# Interfacing_board_updated.net
KiCad netlist of a schematic drawn in EAGLE
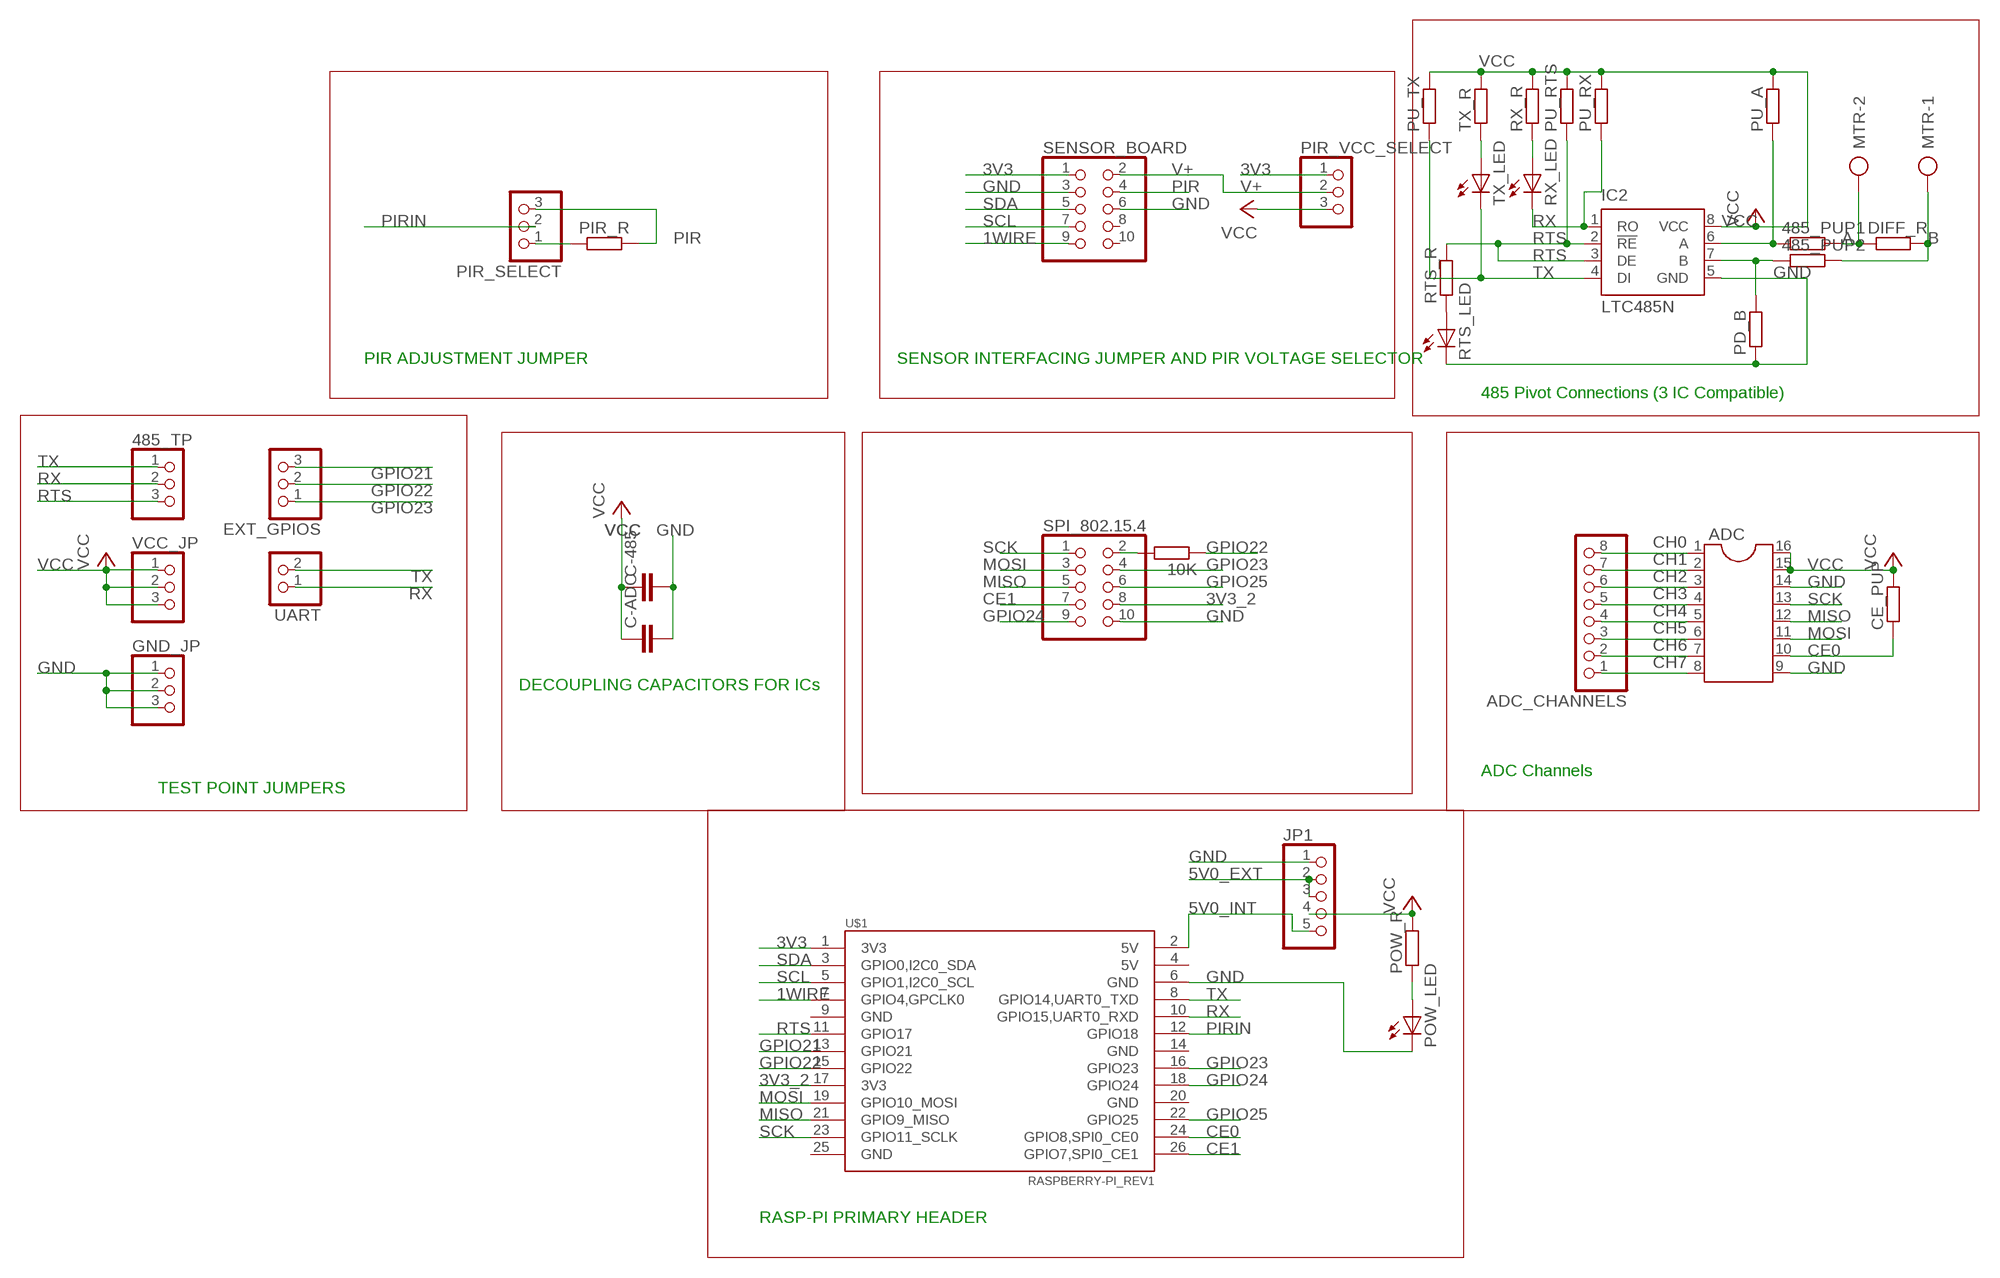
[diagram p0: schematic, sheet 1]

(export (version "E")
  (design (tool "Eeschema 10.0.6"))
  (components
    (comp (ref "10K")
      (value "R-EU_R0603")
      (footprint "eagle-import:R0603")
      (libsource (lib "eagle-import") (part "R-EU_R0603"))
    )
    (comp (ref "485_PUP1")
      (value "R-EU_R0603")
      (footprint "eagle-import:R0603")
      (libsource (lib "eagle-import") (part "R-EU_R0603"))
    )
    (comp (ref "485_PUP2")
      (value "R-EU_R0603")
      (footprint "eagle-import:R0603")
      (libsource (lib "eagle-import") (part "R-EU_R0603"))
    )
    (comp (ref "485_TP")
      (value "PINHD-1X3/90")
      (footprint "eagle-import:1X03_90")
      (libsource (lib "eagle-import") (part "PINHD-1X3/90"))
    )
    (comp (ref "ADC")
      (value "DIL16")
      (footprint "eagle-import:DIL16")
      (libsource (lib "eagle-import") (part "DIL16"))
    )
    (comp (ref "ADC_CHANNELS")
      (value "PINHD-1X8/90")
      (footprint "eagle-import:1X08_90")
      (libsource (lib "eagle-import") (part "PINHD-1X8/90"))
    )
    (comp (ref "C-485")
      (value "C-EU025-025X050")
      (footprint "eagle-import:C025-025X050")
      (libsource (lib "eagle-import") (part "C-EU025-025X050"))
    )
    (comp (ref "C-ADC")
      (value "C-EU025-025X050")
      (footprint "eagle-import:C025-025X050")
      (libsource (lib "eagle-import") (part "C-EU025-025X050"))
    )
    (comp (ref "CE_PUP")
      (value "R-EU_R0603")
      (footprint "eagle-import:R0603")
      (libsource (lib "eagle-import") (part "R-EU_R0603"))
    )
    (comp (ref "DIFF_R")
      (value "R-EU_R0603")
      (footprint "eagle-import:R0603")
      (libsource (lib "eagle-import") (part "R-EU_R0603"))
    )
    (comp (ref "EXT_GPIOS")
      (value "PINHD-1X3/90")
      (footprint "eagle-import:1X03_90")
      (libsource (lib "eagle-import") (part "PINHD-1X3/90"))
    )
    (comp (ref "GND_JP")
      (value "PINHD-1X3/90")
      (footprint "eagle-import:1X03_90")
      (libsource (lib "eagle-import") (part "PINHD-1X3/90"))
    )
    (comp (ref "IC2")
      (value "LTC485N")
      (footprint "eagle-import:DIL08")
      (libsource (lib "eagle-import") (part "LTC485N"))
    )
    (comp (ref "JP1")
      (value "PINHD-1X5")
      (footprint "eagle-import:1X05")
      (libsource (lib "eagle-import") (part "PINHD-1X5"))
    )
    (comp (ref "MTR")
      (value "AK500/2-H")
      (footprint "eagle-import:AK500_2-H")
      (libsource (lib "eagle-import") (part "AK500/2-H"))
    )
    (comp (ref "PD_B")
      (value "R-EU_R0603")
      (footprint "eagle-import:R0603")
      (libsource (lib "eagle-import") (part "R-EU_R0603"))
    )
    (comp (ref "PIR_R")
      (value "R-EU_R0603")
      (footprint "eagle-import:R0603")
      (libsource (lib "eagle-import") (part "R-EU_R0603"))
    )
    (comp (ref "PIR_SELECT")
      (value "PINHD-1X3/90")
      (footprint "eagle-import:1X03_90")
      (libsource (lib "eagle-import") (part "PINHD-1X3/90"))
    )
    (comp (ref "PIR_VCC_SELECT")
      (value "PINHD-1X3/90")
      (footprint "eagle-import:1X03_90")
      (libsource (lib "eagle-import") (part "PINHD-1X3/90"))
    )
    (comp (ref "POW_LED")
      (value "LEDCHIPLED_0805")
      (footprint "eagle-import:CHIPLED_0805")
      (libsource (lib "eagle-import") (part "LEDCHIPLED_0805"))
    )
    (comp (ref "POW_R")
      (value "R-EU_R0603")
      (footprint "eagle-import:R0603")
      (libsource (lib "eagle-import") (part "R-EU_R0603"))
    )
    (comp (ref "PU_A")
      (value "R-EU_R0603")
      (footprint "eagle-import:R0603")
      (libsource (lib "eagle-import") (part "R-EU_R0603"))
    )
    (comp (ref "PU_RTS")
      (value "R-EU_R0603")
      (footprint "eagle-import:R0603")
      (libsource (lib "eagle-import") (part "R-EU_R0603"))
    )
    (comp (ref "PU_RX")
      (value "R-EU_R0603")
      (footprint "eagle-import:R0603")
      (libsource (lib "eagle-import") (part "R-EU_R0603"))
    )
    (comp (ref "PU_TX")
      (value "R-EU_R0603")
      (footprint "eagle-import:R0603")
      (libsource (lib "eagle-import") (part "R-EU_R0603"))
    )
    (comp (ref "RTS_LED")
      (value "LEDCHIPLED_0805")
      (footprint "eagle-import:CHIPLED_0805")
      (libsource (lib "eagle-import") (part "LEDCHIPLED_0805"))
    )
    (comp (ref "RTS_R")
      (value "R-EU_R0603")
      (footprint "eagle-import:R0603")
      (libsource (lib "eagle-import") (part "R-EU_R0603"))
    )
    (comp (ref "RX_LED")
      (value "LEDCHIPLED_0805")
      (footprint "eagle-import:CHIPLED_0805")
      (libsource (lib "eagle-import") (part "LEDCHIPLED_0805"))
    )
    (comp (ref "RX_R")
      (value "R-EU_R0603")
      (footprint "eagle-import:R0603")
      (libsource (lib "eagle-import") (part "R-EU_R0603"))
    )
    (comp (ref "SENSOR_BOARD")
      (value "PINHD-2X5/90")
      (footprint "eagle-import:2X05_90")
      (libsource (lib "eagle-import") (part "PINHD-2X5/90"))
    )
    (comp (ref "SPI_802.15.4")
      (value "PINHD-2X5/90")
      (footprint "eagle-import:2X05_90")
      (libsource (lib "eagle-import") (part "PINHD-2X5/90"))
    )
    (comp (ref "TX_LED")
      (value "LEDCHIPLED_0805")
      (footprint "eagle-import:CHIPLED_0805")
      (libsource (lib "eagle-import") (part "LEDCHIPLED_0805"))
    )
    (comp (ref "TX_R")
      (value "R-EU_R0603")
      (footprint "eagle-import:R0603")
      (libsource (lib "eagle-import") (part "R-EU_R0603"))
    )
    (comp (ref "U$1")
      (value "RASPBERRY-PI_REV1")
      (footprint "eagle-import:RASPBERRY-PI_REV1")
      (libsource (lib "eagle-import") (part "RASPBERRY-PI_REV1"))
    )
    (comp (ref "UART")
      (value "PINHD-1X2")
      (footprint "eagle-import:1X02")
      (libsource (lib "eagle-import") (part "PINHD-1X2"))
    )
    (comp (ref "VCC_JP")
      (value "PINHD-1X3/90")
      (footprint "eagle-import:1X03_90")
      (libsource (lib "eagle-import") (part "PINHD-1X3/90"))
    )
  )
  (nets
    (net (code "1") (name "/1WIRE") (class "Default")
      (node (ref "SENSOR_BOARD") (pin "9") (pinfunction "9_9") (pintype "passive"))
      (node (ref "U$1") (pin "7") (pinfunction "GPIO4,GPCLK0_7") (pintype "bidirectional"))
    )
    (net (code "2") (name "/3V3") (class "Default")
      (node (ref "PIR_VCC_SELECT") (pin "1") (pinfunction "1_1") (pintype "passive"))
      (node (ref "SENSOR_BOARD") (pin "1") (pinfunction "1_1") (pintype "passive"))
      (node (ref "U$1") (pin "1") (pinfunction "3V3_1") (pintype "bidirectional"))
    )
    (net (code "3") (name "/3V3_2") (class "Default")
      (node (ref "SPI_802.15.4") (pin "8") (pinfunction "8_8") (pintype "passive"))
      (node (ref "U$1") (pin "17") (pinfunction "3V3_17") (pintype "bidirectional"))
    )
    (net (code "4") (name "/5V0_EXT") (class "Default")
      (node (ref "JP1") (pin "2") (pinfunction "2_2") (pintype "passive"))
      (node (ref "JP1") (pin "3") (pinfunction "3_3") (pintype "passive"))
    )
    (net (code "5") (name "/5V0_INT") (class "Default")
      (node (ref "JP1") (pin "5") (pinfunction "5_5") (pintype "passive"))
      (node (ref "U$1") (pin "2") (pinfunction "5V_2") (pintype "bidirectional"))
    )
    (net (code "6") (name "/A") (class "Default")
      (node (ref "485_PUP1") (pin "2") (pinfunction "2_2") (pintype "passive"))
      (node (ref "DIFF_R") (pin "1") (pinfunction "1_1") (pintype "passive"))
      (node (ref "MTR") (pin "2") (pinfunction "KL_2") (pintype "passive"))
    )
    (net (code "7") (name "/B") (class "Default")
      (node (ref "485_PUP2") (pin "2") (pinfunction "2_2") (pintype "passive"))
      (node (ref "DIFF_R") (pin "2") (pinfunction "2_2") (pintype "passive"))
      (node (ref "MTR") (pin "1") (pinfunction "KL_1") (pintype "passive"))
    )
    (net (code "8") (name "/CE0") (class "Default")
      (node (ref "ADC") (pin "10") (pinfunction "10_10") (pintype "passive"))
      (node (ref "CE_PUP") (pin "1") (pinfunction "1_1") (pintype "passive"))
      (node (ref "U$1") (pin "24") (pinfunction "GPIO8,SPI0_CE0_24") (pintype "bidirectional"))
    )
    (net (code "9") (name "/CE1") (class "Default")
      (node (ref "SPI_802.15.4") (pin "7") (pinfunction "7_7") (pintype "passive"))
      (node (ref "U$1") (pin "26") (pinfunction "GPIO7,SPI0_CE1_26") (pintype "bidirectional"))
    )
    (net (code "10") (name "/CH0") (class "Default")
      (node (ref "ADC") (pin "1") (pinfunction "1_1") (pintype "passive"))
      (node (ref "ADC_CHANNELS") (pin "8") (pinfunction "8_8") (pintype "passive"))
    )
    (net (code "11") (name "/CH1") (class "Default")
      (node (ref "ADC") (pin "2") (pinfunction "2_2") (pintype "passive"))
      (node (ref "ADC_CHANNELS") (pin "7") (pinfunction "7_7") (pintype "passive"))
    )
    (net (code "12") (name "/CH2") (class "Default")
      (node (ref "ADC") (pin "3") (pinfunction "3_3") (pintype "passive"))
      (node (ref "ADC_CHANNELS") (pin "6") (pinfunction "6_6") (pintype "passive"))
    )
    (net (code "13") (name "/CH3") (class "Default")
      (node (ref "ADC") (pin "4") (pinfunction "4_4") (pintype "passive"))
      (node (ref "ADC_CHANNELS") (pin "5") (pinfunction "5_5") (pintype "passive"))
    )
    (net (code "14") (name "/CH4") (class "Default")
      (node (ref "ADC") (pin "5") (pinfunction "5_5") (pintype "passive"))
      (node (ref "ADC_CHANNELS") (pin "4") (pinfunction "4_4") (pintype "passive"))
    )
    (net (code "15") (name "/CH5") (class "Default")
      (node (ref "ADC") (pin "6") (pinfunction "6_6") (pintype "passive"))
      (node (ref "ADC_CHANNELS") (pin "3") (pinfunction "3_3") (pintype "passive"))
    )
    (net (code "16") (name "/CH6") (class "Default")
      (node (ref "ADC") (pin "7") (pinfunction "7_7") (pintype "passive"))
      (node (ref "ADC_CHANNELS") (pin "2") (pinfunction "2_2") (pintype "passive"))
    )
    (net (code "17") (name "/CH7") (class "Default")
      (node (ref "ADC") (pin "8") (pinfunction "8_8") (pintype "passive"))
      (node (ref "ADC_CHANNELS") (pin "1") (pinfunction "1_1") (pintype "passive"))
    )
    (net (code "18") (name "/GND") (class "Default")
      (node (ref "ADC") (pin "14") (pinfunction "14_14") (pintype "passive"))
      (node (ref "ADC") (pin "9") (pinfunction "9_9") (pintype "passive"))
      (node (ref "C-485") (pin "2") (pinfunction "2_2") (pintype "passive"))
      (node (ref "C-ADC") (pin "2") (pinfunction "2_2") (pintype "passive"))
      (node (ref "GND_JP") (pin "1") (pinfunction "1_1") (pintype "passive"))
      (node (ref "GND_JP") (pin "2") (pinfunction "2_2") (pintype "passive"))
      (node (ref "GND_JP") (pin "3") (pinfunction "3_3") (pintype "passive"))
      (node (ref "IC2") (pin "5") (pinfunction "GND_5") (pintype "input"))
      (node (ref "JP1") (pin "1") (pinfunction "1_1") (pintype "passive"))
      (node (ref "PD_B") (pin "1") (pinfunction "1_1") (pintype "passive"))
      (node (ref "POW_LED") (pin "C") (pinfunction "C_C") (pintype "passive"))
      (node (ref "RTS_LED") (pin "C") (pinfunction "C_C") (pintype "passive"))
      (node (ref "SENSOR_BOARD") (pin "3") (pinfunction "3_3") (pintype "passive"))
      (node (ref "SENSOR_BOARD") (pin "6") (pinfunction "6_6") (pintype "passive"))
      (node (ref "SPI_802.15.4") (pin "10") (pinfunction "10_10") (pintype "passive"))
      (node (ref "U$1") (pin "6") (pinfunction "GND_6") (pintype "bidirectional"))
    )
    (net (code "19") (name "/GPIO21") (class "Default")
      (node (ref "EXT_GPIOS") (pin "3") (pinfunction "3_3") (pintype "passive"))
      (node (ref "U$1") (pin "13") (pinfunction "GPIO21_13") (pintype "bidirectional"))
    )
    (net (code "20") (name "/GPIO22") (class "Default")
      (node (ref "10K") (pin "1") (pinfunction "1_1") (pintype "passive"))
      (node (ref "EXT_GPIOS") (pin "2") (pinfunction "2_2") (pintype "passive"))
      (node (ref "U$1") (pin "15") (pinfunction "GPIO22_15") (pintype "bidirectional"))
    )
    (net (code "21") (name "/GPIO23") (class "Default")
      (node (ref "EXT_GPIOS") (pin "1") (pinfunction "1_1") (pintype "passive"))
      (node (ref "SPI_802.15.4") (pin "4") (pinfunction "4_4") (pintype "passive"))
      (node (ref "U$1") (pin "16") (pinfunction "GPIO23_16") (pintype "bidirectional"))
    )
    (net (code "22") (name "/GPIO24") (class "Default")
      (node (ref "SPI_802.15.4") (pin "9") (pinfunction "9_9") (pintype "passive"))
      (node (ref "U$1") (pin "18") (pinfunction "GPIO24_18") (pintype "bidirectional"))
    )
    (net (code "23") (name "/GPIO25") (class "Default")
      (node (ref "SPI_802.15.4") (pin "6") (pinfunction "6_6") (pintype "passive"))
      (node (ref "U$1") (pin "22") (pinfunction "GPIO25_22") (pintype "bidirectional"))
    )
    (net (code "24") (name "/MISO") (class "Default")
      (node (ref "ADC") (pin "12") (pinfunction "12_12") (pintype "passive"))
      (node (ref "SPI_802.15.4") (pin "5") (pinfunction "5_5") (pintype "passive"))
      (node (ref "U$1") (pin "21") (pinfunction "GPIO9_MISO_21") (pintype "bidirectional"))
    )
    (net (code "25") (name "/MOSI") (class "Default")
      (node (ref "ADC") (pin "11") (pinfunction "11_11") (pintype "passive"))
      (node (ref "SPI_802.15.4") (pin "3") (pinfunction "3_3") (pintype "passive"))
      (node (ref "U$1") (pin "19") (pinfunction "GPIO10_MOSI_19") (pintype "bidirectional"))
    )
    (net (code "26") (name "/PIR") (class "Default")
      (node (ref "PIR_R") (pin "2") (pinfunction "2_2") (pintype "passive"))
      (node (ref "PIR_SELECT") (pin "3") (pinfunction "3_3") (pintype "passive"))
      (node (ref "SENSOR_BOARD") (pin "4") (pinfunction "4_4") (pintype "passive"))
    )
    (net (code "27") (name "/PIRIN") (class "Default")
      (node (ref "PIR_SELECT") (pin "2") (pinfunction "2_2") (pintype "passive"))
      (node (ref "U$1") (pin "12") (pinfunction "GPIO18_12") (pintype "bidirectional"))
    )
    (net (code "28") (name "/RTS") (class "Default")
      (node (ref "485_TP") (pin "3") (pinfunction "3_3") (pintype "passive"))
      (node (ref "IC2") (pin "2") (pinfunction "~{RE}_2") (pintype "input"))
      (node (ref "IC2") (pin "3") (pinfunction "DE_3") (pintype "input"))
      (node (ref "PU_RTS") (pin "1") (pinfunction "1_1") (pintype "passive"))
      (node (ref "RTS_R") (pin "2") (pinfunction "2_2") (pintype "passive"))
      (node (ref "U$1") (pin "11") (pinfunction "GPIO17_11") (pintype "bidirectional"))
    )
    (net (code "29") (name "/RX") (class "Default")
      (node (ref "485_TP") (pin "2") (pinfunction "2_2") (pintype "passive"))
      (node (ref "IC2") (pin "1") (pinfunction "RO_1") (pintype "output"))
      (node (ref "PU_RX") (pin "1") (pinfunction "1_1") (pintype "passive"))
      (node (ref "RX_LED") (pin "C") (pinfunction "C_C") (pintype "passive"))
      (node (ref "U$1") (pin "10") (pinfunction "GPIO15,UART0_RXD_10") (pintype "bidirectional"))
      (node (ref "UART") (pin "1") (pinfunction "1_1") (pintype "passive"))
    )
    (net (code "30") (name "/SCK") (class "Default")
      (node (ref "ADC") (pin "13") (pinfunction "13_13") (pintype "passive"))
      (node (ref "SPI_802.15.4") (pin "1") (pinfunction "1_1") (pintype "passive"))
      (node (ref "U$1") (pin "23") (pinfunction "GPIO11_SCLK_23") (pintype "bidirectional"))
    )
    (net (code "31") (name "/SCL") (class "Default")
      (node (ref "SENSOR_BOARD") (pin "7") (pinfunction "7_7") (pintype "passive"))
      (node (ref "U$1") (pin "5") (pinfunction "GPIO1,I2C0_SCL_5") (pintype "bidirectional"))
    )
    (net (code "32") (name "/SDA") (class "Default")
      (node (ref "SENSOR_BOARD") (pin "5") (pinfunction "5_5") (pintype "passive"))
      (node (ref "U$1") (pin "3") (pinfunction "GPIO0,I2C0_SDA_3") (pintype "bidirectional"))
    )
    (net (code "33") (name "/TX") (class "Default")
      (node (ref "485_TP") (pin "1") (pinfunction "1_1") (pintype "passive"))
      (node (ref "IC2") (pin "4") (pinfunction "DI_4") (pintype "input"))
      (node (ref "PU_TX") (pin "1") (pinfunction "1_1") (pintype "passive"))
      (node (ref "TX_LED") (pin "C") (pinfunction "C_C") (pintype "passive"))
      (node (ref "U$1") (pin "8") (pinfunction "GPIO14,UART0_TXD_8") (pintype "bidirectional"))
      (node (ref "UART") (pin "2") (pinfunction "2_2") (pintype "passive"))
    )
    (net (code "34") (name "/V+") (class "Default")
      (node (ref "PIR_VCC_SELECT") (pin "2") (pinfunction "2_2") (pintype "passive"))
      (node (ref "SENSOR_BOARD") (pin "2") (pinfunction "2_2") (pintype "passive"))
    )
    (net (code "35") (name "Net-(10K-Pad2)") (class "Default")
      (node (ref "10K") (pin "2") (pinfunction "2_2") (pintype "passive"))
      (node (ref "SPI_802.15.4") (pin "2") (pinfunction "2_2") (pintype "passive"))
    )
    (net (code "36") (name "Net-(IC2-A)") (class "Default")
      (node (ref "485_PUP1") (pin "1") (pinfunction "1_1") (pintype "passive"))
      (node (ref "IC2") (pin "6") (pinfunction "A_6") (pintype "bidirectional"))
      (node (ref "PU_A") (pin "1") (pinfunction "1_1") (pintype "passive"))
    )
    (net (code "37") (name "Net-(IC2-B)") (class "Default")
      (node (ref "485_PUP2") (pin "1") (pinfunction "1_1") (pintype "passive"))
      (node (ref "IC2") (pin "7") (pinfunction "B_7") (pintype "bidirectional"))
      (node (ref "PD_B") (pin "2") (pinfunction "2_2") (pintype "passive"))
    )
    (net (code "38") (name "Net-(PIR_R-Pad1)") (class "Default")
      (node (ref "PIR_R") (pin "1") (pinfunction "1_1") (pintype "passive"))
      (node (ref "PIR_SELECT") (pin "1") (pinfunction "1_1") (pintype "passive"))
    )
    (net (code "39") (name "Net-(POW_LED-PadA)") (class "Default")
      (node (ref "POW_LED") (pin "A") (pinfunction "A_A") (pintype "passive"))
      (node (ref "POW_R") (pin "1") (pinfunction "1_1") (pintype "passive"))
    )
    (net (code "40") (name "Net-(RTS_LED-PadA)") (class "Default")
      (node (ref "RTS_LED") (pin "A") (pinfunction "A_A") (pintype "passive"))
      (node (ref "RTS_R") (pin "1") (pinfunction "1_1") (pintype "passive"))
    )
    (net (code "41") (name "Net-(RX_LED-PadA)") (class "Default")
      (node (ref "RX_LED") (pin "A") (pinfunction "A_A") (pintype "passive"))
      (node (ref "RX_R") (pin "1") (pinfunction "1_1") (pintype "passive"))
    )
    (net (code "42") (name "Net-(TX_LED-PadA)") (class "Default")
      (node (ref "TX_LED") (pin "A") (pinfunction "A_A") (pintype "passive"))
      (node (ref "TX_R") (pin "1") (pinfunction "1_1") (pintype "passive"))
    )
    (net (code "43") (name "VCC") (class "Default")
      (node (ref "ADC") (pin "15") (pinfunction "15_15") (pintype "passive"))
      (node (ref "ADC") (pin "16") (pinfunction "16_16") (pintype "passive"))
      (node (ref "C-485") (pin "1") (pinfunction "1_1") (pintype "passive"))
      (node (ref "C-ADC") (pin "1") (pinfunction "1_1") (pintype "passive"))
      (node (ref "CE_PUP") (pin "2") (pinfunction "2_2") (pintype "passive"))
      (node (ref "IC2") (pin "8") (pinfunction "VCC_8") (pintype "input"))
      (node (ref "JP1") (pin "4") (pinfunction "4_4") (pintype "passive"))
      (node (ref "PIR_VCC_SELECT") (pin "3") (pinfunction "3_3") (pintype "passive"))
      (node (ref "POW_R") (pin "2") (pinfunction "2_2") (pintype "passive"))
      (node (ref "PU_A") (pin "2") (pinfunction "2_2") (pintype "passive"))
      (node (ref "PU_RTS") (pin "2") (pinfunction "2_2") (pintype "passive"))
      (node (ref "PU_RX") (pin "2") (pinfunction "2_2") (pintype "passive"))
      (node (ref "PU_TX") (pin "2") (pinfunction "2_2") (pintype "passive"))
      (node (ref "RX_R") (pin "2") (pinfunction "2_2") (pintype "passive"))
      (node (ref "TX_R") (pin "2") (pinfunction "2_2") (pintype "passive"))
      (node (ref "VCC_JP") (pin "1") (pinfunction "1_1") (pintype "passive"))
      (node (ref "VCC_JP") (pin "2") (pinfunction "2_2") (pintype "passive"))
      (node (ref "VCC_JP") (pin "3") (pinfunction "3_3") (pintype "passive"))
    )
    (net (code "44") (name "unconnected-(SENSOR_BOARD-Pad8)") (class "Default")
      (node (ref "SENSOR_BOARD") (pin "8") (pinfunction "8_8") (pintype "passive"))
    )
    (net (code "45") (name "unconnected-(SENSOR_BOARD-Pad10)") (class "Default")
      (node (ref "SENSOR_BOARD") (pin "10") (pinfunction "10_10") (pintype "passive"))
    )
    (net (code "46") (name "unconnected-(U$1-5V-Pad4)") (class "Default")
      (node (ref "U$1") (pin "4") (pinfunction "5V_4") (pintype "bidirectional"))
    )
    (net (code "47") (name "unconnected-(U$1-GND-Pad9)") (class "Default")
      (node (ref "U$1") (pin "9") (pinfunction "GND_9") (pintype "bidirectional"))
    )
    (net (code "48") (name "unconnected-(U$1-GND-Pad14)") (class "Default")
      (node (ref "U$1") (pin "14") (pinfunction "GND_14") (pintype "bidirectional"))
    )
    (net (code "49") (name "unconnected-(U$1-GND-Pad20)") (class "Default")
      (node (ref "U$1") (pin "20") (pinfunction "GND_20") (pintype "bidirectional"))
    )
    (net (code "50") (name "unconnected-(U$1-GND-Pad25)") (class "Default")
      (node (ref "U$1") (pin "25") (pinfunction "GND_25") (pintype "bidirectional"))
    )
  )
)
